# Temp.net
KiCad netlist of a schematic drawn in EAGLE
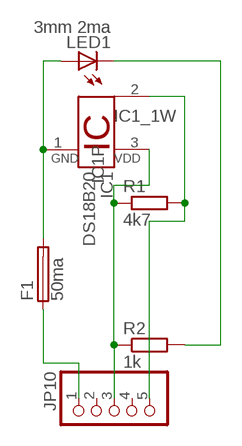
[diagram p0: schematic, sheet 1]

(export (version "E")
  (design (tool "Eeschema 10.0.6"))
  (components
    (comp (ref "F1")
      (value "50ma")
      (footprint "eagle-import:MF-SMDF050")
      (libsource (lib "eagle-import") (part "MF-SMDF050"))
    )
    (comp (ref "IC1")
      (value "DS18B20")
      (footprint "eagle-import:TO92-")
      (libsource (lib "eagle-import") (part "DS18B20"))
    )
    (comp (ref "JP10")
      (value "PINHD-1X5")
      (footprint "eagle-import:1X05")
      (libsource (lib "eagle-import") (part "PINHD-1X5"))
    )
    (comp (ref "LED1")
      (value "3mm 2ma")
      (footprint "eagle-import:LED3MM")
      (fields (field (name "MF") "VISHAY SEMICONDUCTOR"))
      (libsource (lib "eagle-import") (part "TLLY4400"))
    )
    (comp (ref "R1")
      (value "4k7")
      (footprint "eagle-import:R1206")
      (libsource (lib "eagle-import") (part "R-EU_R1206"))
    )
    (comp (ref "R2")
      (value "1k")
      (footprint "eagle-import:R1206")
      (libsource (lib "eagle-import") (part "R-EU_R1206"))
    )
  )
  (nets
    (net (code "1") (name "Net-(F1-Pad1)") (class "Default")
      (node (ref "F1") (pin "1") (pinfunction "1_1") (pintype "passive"))
      (node (ref "JP10") (pin "1") (pinfunction "1_1") (pintype "passive"))
    )
    (net (code "2") (name "Net-(IC1B-GND)") (class "Default")
      (node (ref "F1") (pin "2") (pinfunction "2_2") (pintype "passive"))
      (node (ref "IC1") (pin "1") (pinfunction "GND_1") (pintype "power_in"))
      (node (ref "LED1") (pin "A") (pinfunction "A_A") (pintype "passive"))
    )
    (net (code "3") (name "Net-(IC1B-VDD)") (class "Default")
      (node (ref "IC1") (pin "3") (pinfunction "VDD_3") (pintype "power_in"))
      (node (ref "JP10") (pin "3") (pinfunction "3_3") (pintype "passive"))
      (node (ref "R1") (pin "1") (pinfunction "1_1") (pintype "passive"))
      (node (ref "R2") (pin "1") (pinfunction "1_1") (pintype "passive"))
    )
    (net (code "4") (name "Net-(IC1C-1W)") (class "Default")
      (node (ref "IC1") (pin "2") (pinfunction "1W_2") (pintype "power_in"))
      (node (ref "JP10") (pin "5") (pinfunction "5_5") (pintype "passive"))
      (node (ref "R1") (pin "2") (pinfunction "2_2") (pintype "passive"))
    )
    (net (code "5") (name "Net-(LED1-C)") (class "Default")
      (node (ref "LED1") (pin "K") (pinfunction "C_K") (pintype "passive"))
      (node (ref "R2") (pin "2") (pinfunction "2_2") (pintype "passive"))
    )
    (net (code "6") (name "unconnected-(JP10-Pad2)") (class "Default")
      (node (ref "JP10") (pin "2") (pinfunction "2_2") (pintype "passive"))
    )
    (net (code "7") (name "unconnected-(JP10-Pad4)") (class "Default")
      (node (ref "JP10") (pin "4") (pinfunction "4_4") (pintype "passive"))
    )
  )
)
